# analog.net
KiCad netlist of a schematic drawn in EAGLE
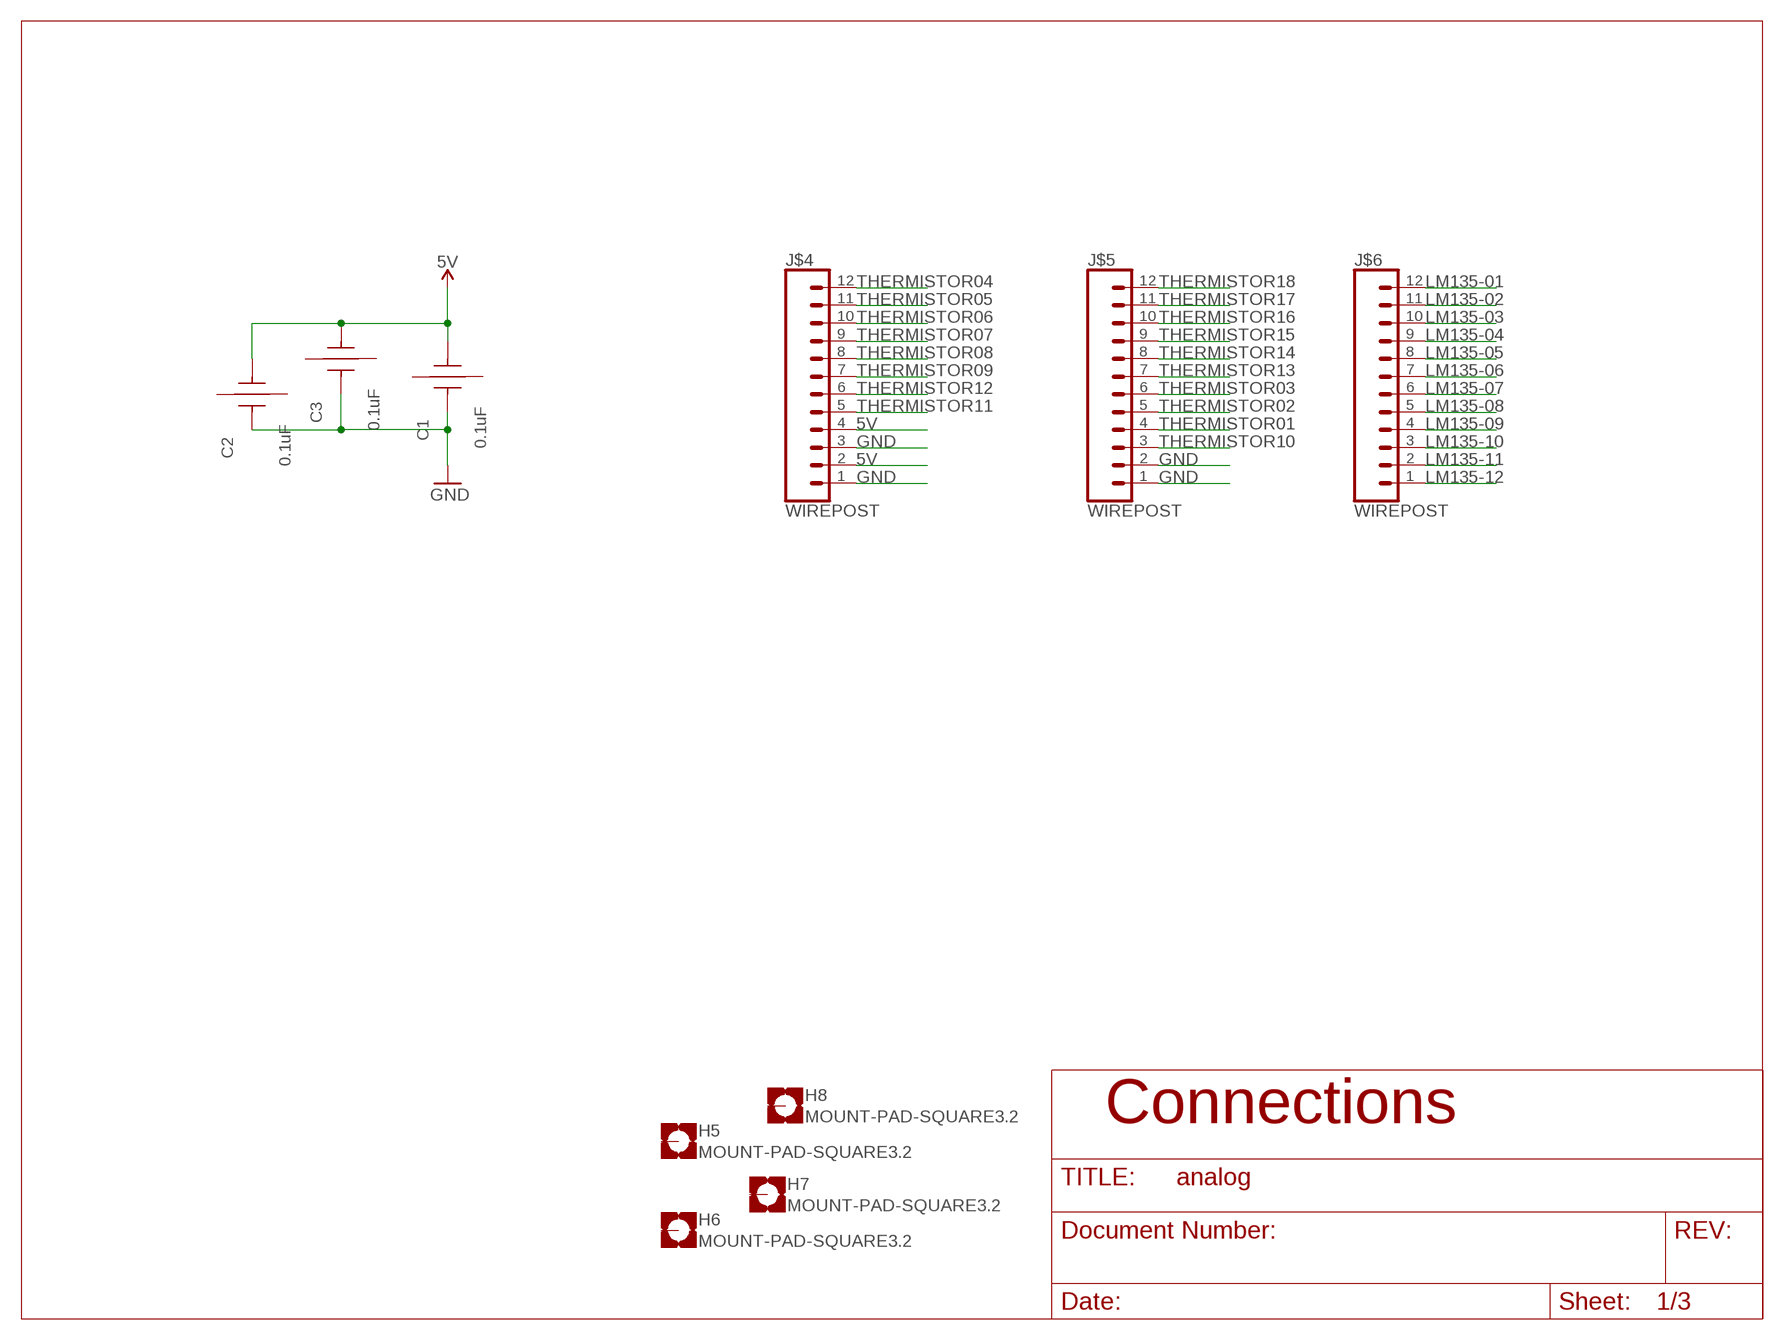
[diagram p0: schematic, sheet 1]
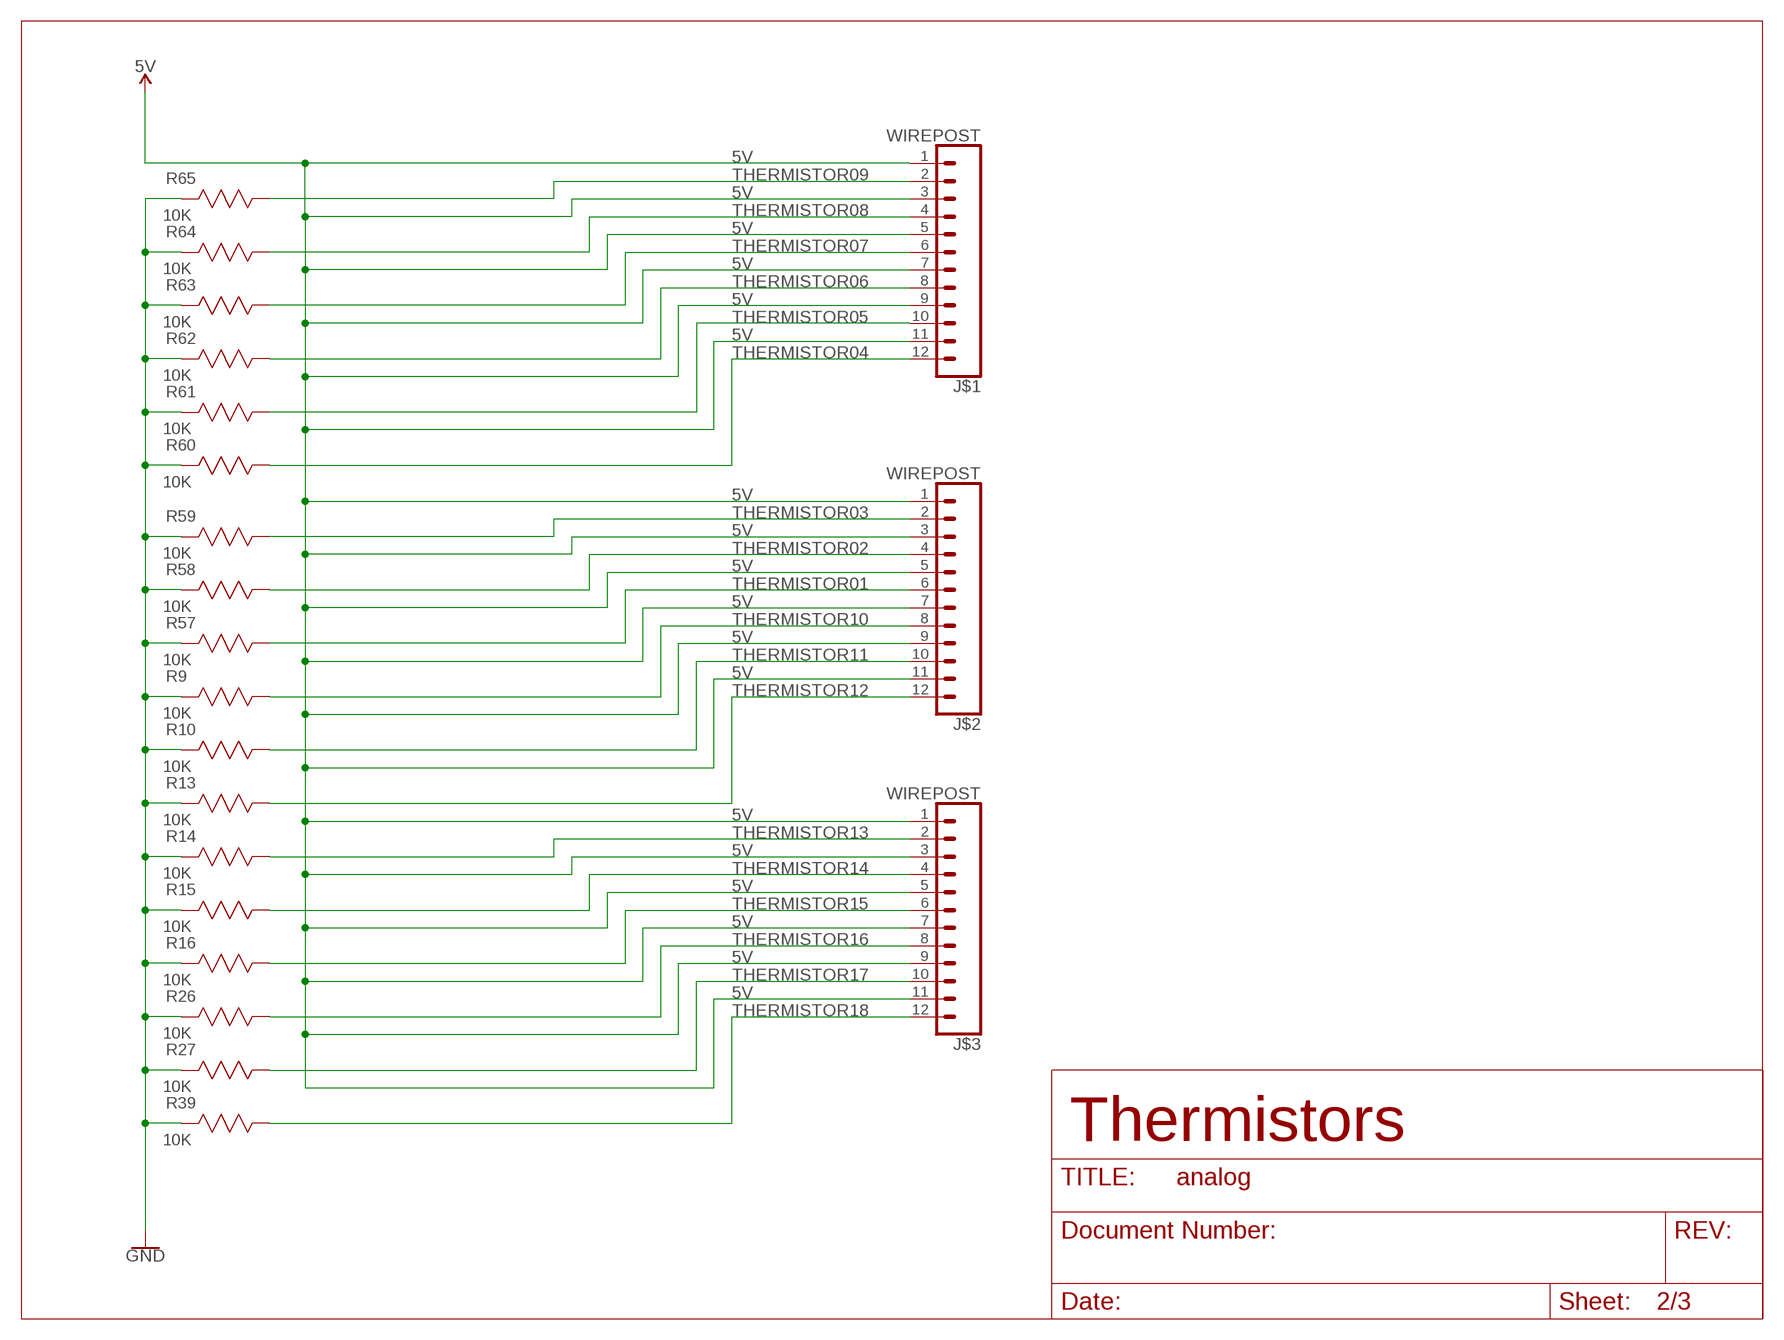
[diagram p1: schematic, sheet 2]
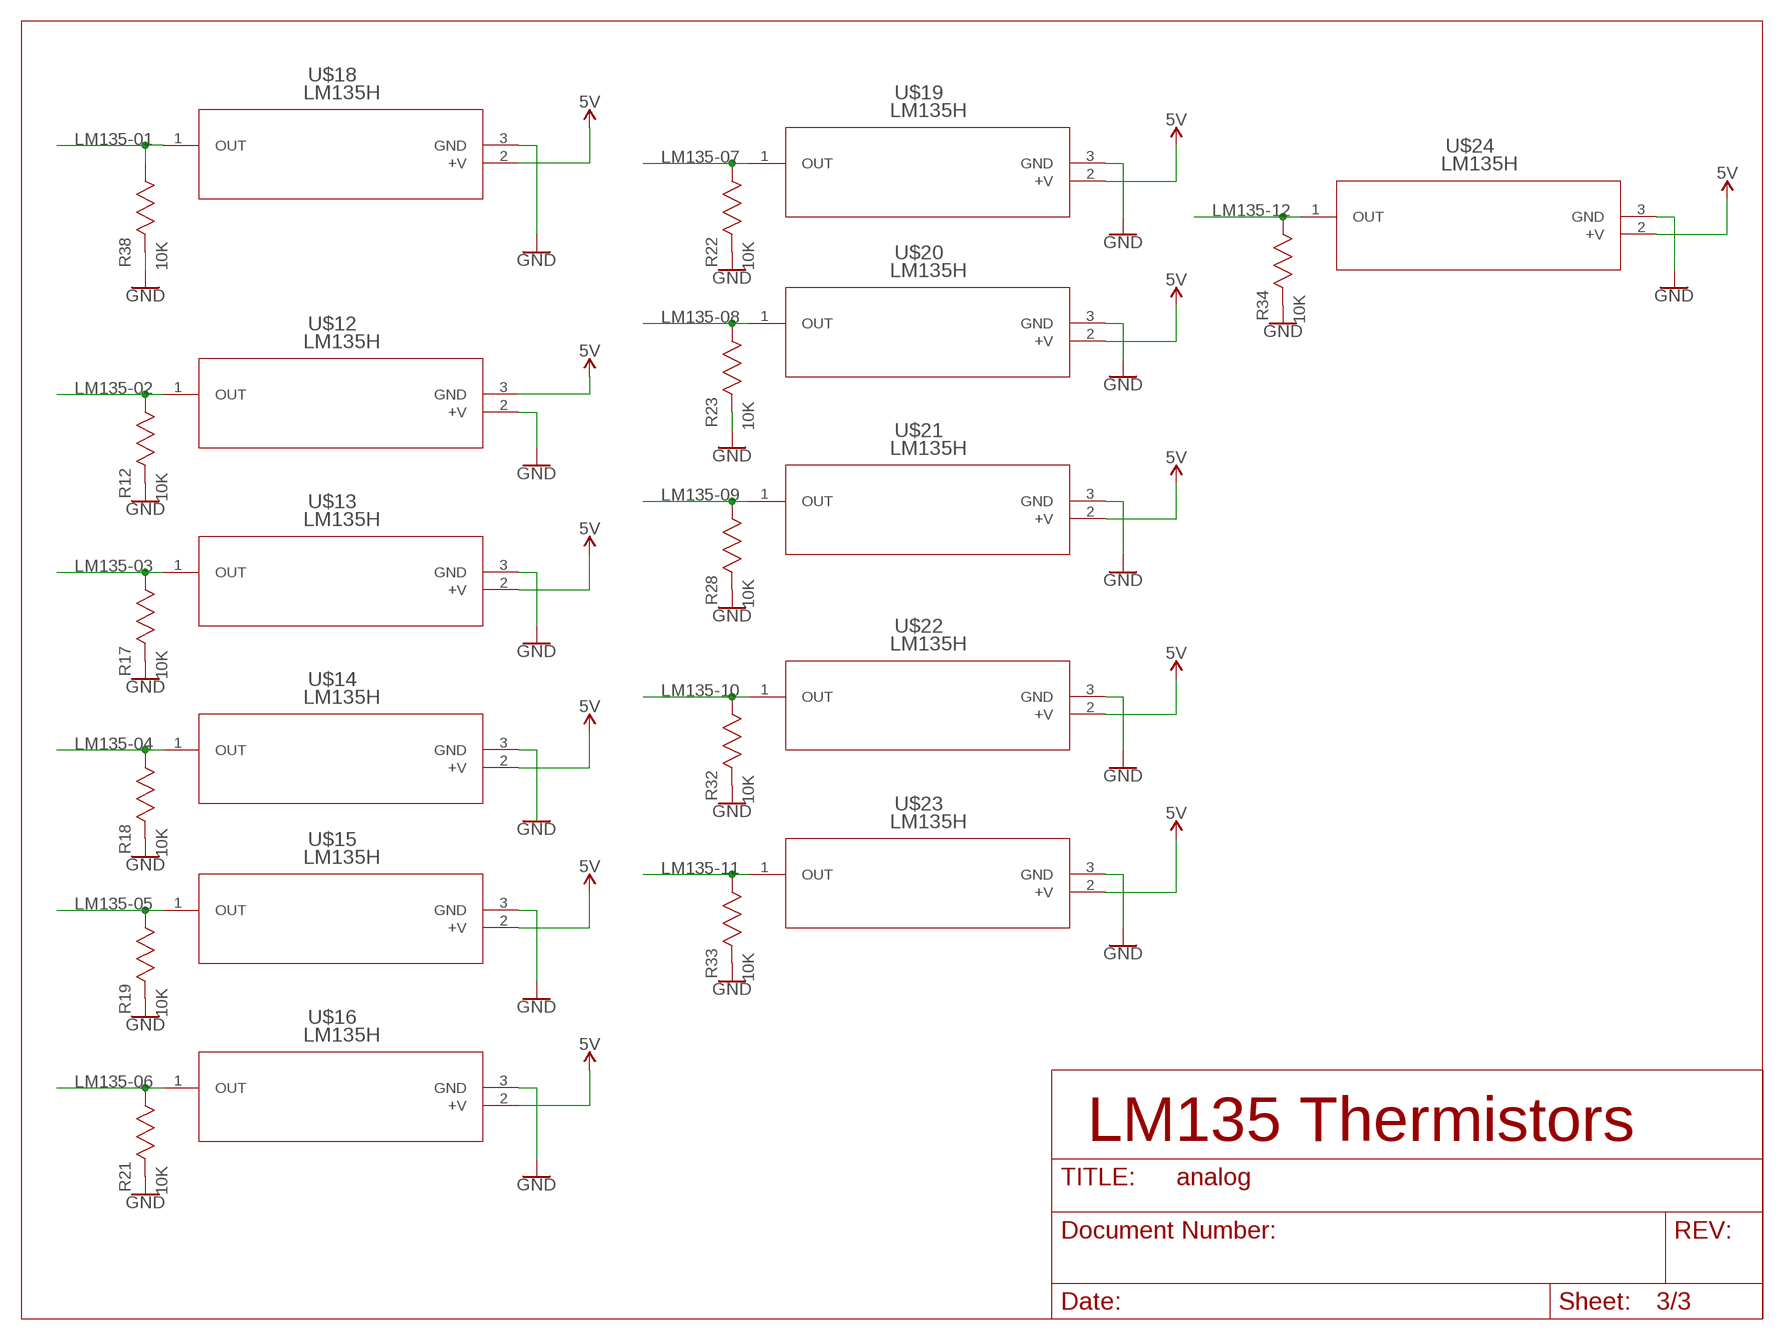
[diagram p2: schematic, sheet 3]

(export (version "E")
  (design (tool "Eeschema 10.0.6"))
  (components
    (comp (ref "J$1")
      (value "WIREPOST")
      (footprint "eagle-import:WIREWRAPPOST")
      (libsource (lib "eagle-import") (part "WIREPOST"))
    )
    (comp (ref "J$2")
      (value "WIREPOST")
      (footprint "eagle-import:WIREWRAPPOST")
      (libsource (lib "eagle-import") (part "WIREPOST"))
    )
    (comp (ref "J$3")
      (value "WIREPOST")
      (footprint "eagle-import:WIREWRAPPOST")
      (libsource (lib "eagle-import") (part "WIREPOST"))
    )
    (comp (ref "R9")
      (value "10K")
      (footprint "eagle-import:RC0603N")
      (fields (field (name "MANUFACTURER_PART_NUMBER") "RC0603JR0710KL"))
      (libsource (lib "eagle-import") (part "RC0603JR-0710KL"))
    )
    (comp (ref "R10")
      (value "10K")
      (footprint "eagle-import:RC0603N")
      (fields (field (name "MANUFACTURER_PART_NUMBER") "RC0603JR0710KL"))
      (libsource (lib "eagle-import") (part "RC0603JR-0710KL"))
    )
    (comp (ref "R13")
      (value "10K")
      (footprint "eagle-import:RC0603N")
      (fields (field (name "MANUFACTURER_PART_NUMBER") "RC0603JR0710KL"))
      (libsource (lib "eagle-import") (part "RC0603JR-0710KL"))
    )
    (comp (ref "R14")
      (value "10K")
      (footprint "eagle-import:RC0603N")
      (fields (field (name "MANUFACTURER_PART_NUMBER") "RC0603JR0710KL"))
      (libsource (lib "eagle-import") (part "RC0603JR-0710KL"))
    )
    (comp (ref "R15")
      (value "10K")
      (footprint "eagle-import:RC0603N")
      (fields (field (name "MANUFACTURER_PART_NUMBER") "RC0603JR0710KL"))
      (libsource (lib "eagle-import") (part "RC0603JR-0710KL"))
    )
    (comp (ref "R16")
      (value "10K")
      (footprint "eagle-import:RC0603N")
      (fields (field (name "MANUFACTURER_PART_NUMBER") "RC0603JR0710KL"))
      (libsource (lib "eagle-import") (part "RC0603JR-0710KL"))
    )
    (comp (ref "R26")
      (value "10K")
      (footprint "eagle-import:RC0603N")
      (fields (field (name "MANUFACTURER_PART_NUMBER") "RC0603JR0710KL"))
      (libsource (lib "eagle-import") (part "RC0603JR-0710KL"))
    )
    (comp (ref "R27")
      (value "10K")
      (footprint "eagle-import:RC0603N")
      (fields (field (name "MANUFACTURER_PART_NUMBER") "RC0603JR0710KL"))
      (libsource (lib "eagle-import") (part "RC0603JR-0710KL"))
    )
    (comp (ref "R39")
      (value "10K")
      (footprint "eagle-import:RC0603N")
      (fields (field (name "MANUFACTURER_PART_NUMBER") "RC0603JR0710KL"))
      (libsource (lib "eagle-import") (part "RC0603JR-0710KL"))
    )
    (comp (ref "R57")
      (value "10K")
      (footprint "eagle-import:RC0603N")
      (fields (field (name "MANUFACTURER_PART_NUMBER") "RC0603JR0710KL"))
      (libsource (lib "eagle-import") (part "RC0603JR-0710KL"))
    )
    (comp (ref "R58")
      (value "10K")
      (footprint "eagle-import:RC0603N")
      (fields (field (name "MANUFACTURER_PART_NUMBER") "RC0603JR0710KL"))
      (libsource (lib "eagle-import") (part "RC0603JR-0710KL"))
    )
    (comp (ref "R59")
      (value "10K")
      (footprint "eagle-import:RC0603N")
      (fields (field (name "MANUFACTURER_PART_NUMBER") "RC0603JR0710KL"))
      (libsource (lib "eagle-import") (part "RC0603JR-0710KL"))
    )
    (comp (ref "R60")
      (value "10K")
      (footprint "eagle-import:RC0603N")
      (fields (field (name "MANUFACTURER_PART_NUMBER") "RC0603JR0710KL"))
      (libsource (lib "eagle-import") (part "RC0603JR-0710KL"))
    )
    (comp (ref "R61")
      (value "10K")
      (footprint "eagle-import:RC0603N")
      (fields (field (name "MANUFACTURER_PART_NUMBER") "RC0603JR0710KL"))
      (libsource (lib "eagle-import") (part "RC0603JR-0710KL"))
    )
    (comp (ref "R62")
      (value "10K")
      (footprint "eagle-import:RC0603N")
      (fields (field (name "MANUFACTURER_PART_NUMBER") "RC0603JR0710KL"))
      (libsource (lib "eagle-import") (part "RC0603JR-0710KL"))
    )
    (comp (ref "R63")
      (value "10K")
      (footprint "eagle-import:RC0603N")
      (fields (field (name "MANUFACTURER_PART_NUMBER") "RC0603JR0710KL"))
      (libsource (lib "eagle-import") (part "RC0603JR-0710KL"))
    )
    (comp (ref "R64")
      (value "10K")
      (footprint "eagle-import:RC0603N")
      (fields (field (name "MANUFACTURER_PART_NUMBER") "RC0603JR0710KL"))
      (libsource (lib "eagle-import") (part "RC0603JR-0710KL"))
    )
    (comp (ref "R65")
      (value "10K")
      (footprint "eagle-import:RC0603N")
      (fields (field (name "MANUFACTURER_PART_NUMBER") "RC0603JR0710KL"))
      (libsource (lib "eagle-import") (part "RC0603JR-0710KL"))
    )
    (comp (ref "C1")
      (value "0.1uF")
      (footprint "eagle-import:X14")
      (fields (field (name "MANUFACTURER_PART_NUMBER") "100X14W104MV4T"))
      (libsource (lib "eagle-import") (part "100X14W104MV4T"))
    )
    (comp (ref "C2")
      (value "0.1uF")
      (footprint "eagle-import:X14")
      (fields (field (name "MANUFACTURER_PART_NUMBER") "100X14W104MV4T"))
      (libsource (lib "eagle-import") (part "100X14W104MV4T"))
    )
    (comp (ref "C3")
      (value "0.1uF")
      (footprint "eagle-import:X14")
      (fields (field (name "MANUFACTURER_PART_NUMBER") "100X14W104MV4T"))
      (libsource (lib "eagle-import") (part "100X14W104MV4T"))
    )
    (comp (ref "H5")
      (value "MOUNT-PAD-SQUARE3.2")
      (footprint "eagle-import:3,2-PAD-SQUARE")
      (libsource (lib "eagle-import") (part "MOUNT-PAD-SQUARE3.2"))
    )
    (comp (ref "H6")
      (value "MOUNT-PAD-SQUARE3.2")
      (footprint "eagle-import:3,2-PAD-SQUARE")
      (libsource (lib "eagle-import") (part "MOUNT-PAD-SQUARE3.2"))
    )
    (comp (ref "H7")
      (value "MOUNT-PAD-SQUARE3.2")
      (footprint "eagle-import:3,2-PAD-SQUARE")
      (libsource (lib "eagle-import") (part "MOUNT-PAD-SQUARE3.2"))
    )
    (comp (ref "H8")
      (value "MOUNT-PAD-SQUARE3.2")
      (footprint "eagle-import:3,2-PAD-SQUARE")
      (libsource (lib "eagle-import") (part "MOUNT-PAD-SQUARE3.2"))
    )
    (comp (ref "J$4")
      (value "WIREPOST")
      (footprint "eagle-import:WIREWRAPPOST")
      (libsource (lib "eagle-import") (part "WIREPOST"))
    )
    (comp (ref "J$5")
      (value "WIREPOST")
      (footprint "eagle-import:WIREWRAPPOST")
      (libsource (lib "eagle-import") (part "WIREPOST"))
    )
    (comp (ref "J$6")
      (value "WIREPOST")
      (footprint "eagle-import:WIREWRAPPOST")
      (libsource (lib "eagle-import") (part "WIREPOST"))
    )
    (comp (ref "R12")
      (value "10K")
      (footprint "eagle-import:RC0603N")
      (fields (field (name "MANUFACTURER_PART_NUMBER") "RC0603JR0710KL"))
      (libsource (lib "eagle-import") (part "RC0603JR-0710KL"))
    )
    (comp (ref "R17")
      (value "10K")
      (footprint "eagle-import:RC0603N")
      (fields (field (name "MANUFACTURER_PART_NUMBER") "RC0603JR0710KL"))
      (libsource (lib "eagle-import") (part "RC0603JR-0710KL"))
    )
    (comp (ref "R18")
      (value "10K")
      (footprint "eagle-import:RC0603N")
      (fields (field (name "MANUFACTURER_PART_NUMBER") "RC0603JR0710KL"))
      (libsource (lib "eagle-import") (part "RC0603JR-0710KL"))
    )
    (comp (ref "R19")
      (value "10K")
      (footprint "eagle-import:RC0603N")
      (fields (field (name "MANUFACTURER_PART_NUMBER") "RC0603JR0710KL"))
      (libsource (lib "eagle-import") (part "RC0603JR-0710KL"))
    )
    (comp (ref "R21")
      (value "10K")
      (footprint "eagle-import:RC0603N")
      (fields (field (name "MANUFACTURER_PART_NUMBER") "RC0603JR0710KL"))
      (libsource (lib "eagle-import") (part "RC0603JR-0710KL"))
    )
    (comp (ref "R22")
      (value "10K")
      (footprint "eagle-import:RC0603N")
      (fields (field (name "MANUFACTURER_PART_NUMBER") "RC0603JR0710KL"))
      (libsource (lib "eagle-import") (part "RC0603JR-0710KL"))
    )
    (comp (ref "R23")
      (value "10K")
      (footprint "eagle-import:RC0603N")
      (fields (field (name "MANUFACTURER_PART_NUMBER") "RC0603JR0710KL"))
      (libsource (lib "eagle-import") (part "RC0603JR-0710KL"))
    )
    (comp (ref "R28")
      (value "10K")
      (footprint "eagle-import:RC0603N")
      (fields (field (name "MANUFACTURER_PART_NUMBER") "RC0603JR0710KL"))
      (libsource (lib "eagle-import") (part "RC0603JR-0710KL"))
    )
    (comp (ref "R32")
      (value "10K")
      (footprint "eagle-import:RC0603N")
      (fields (field (name "MANUFACTURER_PART_NUMBER") "RC0603JR0710KL"))
      (libsource (lib "eagle-import") (part "RC0603JR-0710KL"))
    )
    (comp (ref "R33")
      (value "10K")
      (footprint "eagle-import:RC0603N")
      (fields (field (name "MANUFACTURER_PART_NUMBER") "RC0603JR0710KL"))
      (libsource (lib "eagle-import") (part "RC0603JR-0710KL"))
    )
    (comp (ref "R34")
      (value "10K")
      (footprint "eagle-import:RC0603N")
      (fields (field (name "MANUFACTURER_PART_NUMBER") "RC0603JR0710KL"))
      (libsource (lib "eagle-import") (part "RC0603JR-0710KL"))
    )
    (comp (ref "R38")
      (value "10K")
      (footprint "eagle-import:RC0603N")
      (fields (field (name "MANUFACTURER_PART_NUMBER") "RC0603JR0710KL"))
      (libsource (lib "eagle-import") (part "RC0603JR-0710KL"))
    )
    (comp (ref "U$12")
      (value "LM135H")
      (footprint "eagle-import:TO46")
      (libsource (lib "eagle-import") (part "LM135H"))
    )
    (comp (ref "U$13")
      (value "LM135H")
      (footprint "eagle-import:TO46")
      (libsource (lib "eagle-import") (part "LM135H"))
    )
    (comp (ref "U$14")
      (value "LM135H")
      (footprint "eagle-import:TO46")
      (libsource (lib "eagle-import") (part "LM135H"))
    )
    (comp (ref "U$15")
      (value "LM135H")
      (footprint "eagle-import:TO46")
      (libsource (lib "eagle-import") (part "LM135H"))
    )
    (comp (ref "U$16")
      (value "LM135H")
      (footprint "eagle-import:TO46")
      (libsource (lib "eagle-import") (part "LM135H"))
    )
    (comp (ref "U$18")
      (value "LM135H")
      (footprint "eagle-import:TO46")
      (libsource (lib "eagle-import") (part "LM135H"))
    )
    (comp (ref "U$19")
      (value "LM135H")
      (footprint "eagle-import:TO46")
      (libsource (lib "eagle-import") (part "LM135H"))
    )
    (comp (ref "U$20")
      (value "LM135H")
      (footprint "eagle-import:TO46")
      (libsource (lib "eagle-import") (part "LM135H"))
    )
    (comp (ref "U$21")
      (value "LM135H")
      (footprint "eagle-import:TO46")
      (libsource (lib "eagle-import") (part "LM135H"))
    )
    (comp (ref "U$22")
      (value "LM135H")
      (footprint "eagle-import:TO46")
      (libsource (lib "eagle-import") (part "LM135H"))
    )
    (comp (ref "U$23")
      (value "LM135H")
      (footprint "eagle-import:TO46")
      (libsource (lib "eagle-import") (part "LM135H"))
    )
    (comp (ref "U$24")
      (value "LM135H")
      (footprint "eagle-import:TO46")
      (libsource (lib "eagle-import") (part "LM135H"))
    )
  )
  (nets
    (net (code "1") (name "5V") (class "Default")
      (node (ref "C1") (pin "2") (pinfunction "22_2") (pintype "passive"))
      (node (ref "C2") (pin "2") (pinfunction "22_2") (pintype "passive"))
      (node (ref "C3") (pin "2") (pinfunction "22_2") (pintype "passive"))
      (node (ref "J$1") (pin "1") (pinfunction "1_1") (pintype "passive"))
      (node (ref "J$1") (pin "11") (pinfunction "11_11") (pintype "passive"))
      (node (ref "J$1") (pin "3") (pinfunction "3_3") (pintype "passive"))
      (node (ref "J$1") (pin "5") (pinfunction "5_5") (pintype "passive"))
      (node (ref "J$1") (pin "7") (pinfunction "7_7") (pintype "passive"))
      (node (ref "J$1") (pin "9") (pinfunction "9_9") (pintype "passive"))
      (node (ref "J$2") (pin "1") (pinfunction "1_1") (pintype "passive"))
      (node (ref "J$2") (pin "11") (pinfunction "11_11") (pintype "passive"))
      (node (ref "J$2") (pin "3") (pinfunction "3_3") (pintype "passive"))
      (node (ref "J$2") (pin "5") (pinfunction "5_5") (pintype "passive"))
      (node (ref "J$2") (pin "7") (pinfunction "7_7") (pintype "passive"))
      (node (ref "J$2") (pin "9") (pinfunction "9_9") (pintype "passive"))
      (node (ref "J$3") (pin "1") (pinfunction "1_1") (pintype "passive"))
      (node (ref "J$3") (pin "11") (pinfunction "11_11") (pintype "passive"))
      (node (ref "J$3") (pin "3") (pinfunction "3_3") (pintype "passive"))
      (node (ref "J$3") (pin "5") (pinfunction "5_5") (pintype "passive"))
      (node (ref "J$3") (pin "7") (pinfunction "7_7") (pintype "passive"))
      (node (ref "J$3") (pin "9") (pinfunction "9_9") (pintype "passive"))
      (node (ref "J$4") (pin "2") (pinfunction "2_2") (pintype "passive"))
      (node (ref "J$4") (pin "4") (pinfunction "4_4") (pintype "passive"))
      (node (ref "U$12") (pin "3") (pinfunction "GND_3") (pintype "passive"))
      (node (ref "U$13") (pin "2") (pinfunction "+V_2") (pintype "passive"))
      (node (ref "U$14") (pin "2") (pinfunction "+V_2") (pintype "passive"))
      (node (ref "U$15") (pin "2") (pinfunction "+V_2") (pintype "passive"))
      (node (ref "U$16") (pin "2") (pinfunction "+V_2") (pintype "passive"))
      (node (ref "U$18") (pin "2") (pinfunction "+V_2") (pintype "passive"))
      (node (ref "U$19") (pin "2") (pinfunction "+V_2") (pintype "passive"))
      (node (ref "U$20") (pin "2") (pinfunction "+V_2") (pintype "passive"))
      (node (ref "U$21") (pin "2") (pinfunction "+V_2") (pintype "passive"))
      (node (ref "U$22") (pin "2") (pinfunction "+V_2") (pintype "passive"))
      (node (ref "U$23") (pin "2") (pinfunction "+V_2") (pintype "passive"))
      (node (ref "U$24") (pin "2") (pinfunction "+V_2") (pintype "passive"))
    )
    (net (code "2") (name "GND") (class "Default")
      (node (ref "C1") (pin "1") (pinfunction "11_1") (pintype "passive"))
      (node (ref "C2") (pin "1") (pinfunction "11_1") (pintype "passive"))
      (node (ref "C3") (pin "1") (pinfunction "11_1") (pintype "passive"))
      (node (ref "J$4") (pin "1") (pinfunction "1_1") (pintype "passive"))
      (node (ref "J$4") (pin "3") (pinfunction "3_3") (pintype "passive"))
      (node (ref "J$5") (pin "1") (pinfunction "1_1") (pintype "passive"))
      (node (ref "J$5") (pin "2") (pinfunction "2_2") (pintype "passive"))
      (node (ref "R10") (pin "2") (pinfunction "22_2") (pintype "passive"))
      (node (ref "R12") (pin "2") (pinfunction "22_2") (pintype "passive"))
      (node (ref "R13") (pin "2") (pinfunction "22_2") (pintype "passive"))
      (node (ref "R14") (pin "2") (pinfunction "22_2") (pintype "passive"))
      (node (ref "R15") (pin "2") (pinfunction "22_2") (pintype "passive"))
      (node (ref "R16") (pin "2") (pinfunction "22_2") (pintype "passive"))
      (node (ref "R17") (pin "2") (pinfunction "22_2") (pintype "passive"))
      (node (ref "R18") (pin "2") (pinfunction "22_2") (pintype "passive"))
      (node (ref "R19") (pin "2") (pinfunction "22_2") (pintype "passive"))
      (node (ref "R21") (pin "2") (pinfunction "22_2") (pintype "passive"))
      (node (ref "R22") (pin "2") (pinfunction "22_2") (pintype "passive"))
      (node (ref "R23") (pin "2") (pinfunction "22_2") (pintype "passive"))
      (node (ref "R26") (pin "2") (pinfunction "22_2") (pintype "passive"))
      (node (ref "R27") (pin "2") (pinfunction "22_2") (pintype "passive"))
      (node (ref "R28") (pin "2") (pinfunction "22_2") (pintype "passive"))
      (node (ref "R32") (pin "2") (pinfunction "22_2") (pintype "passive"))
      (node (ref "R33") (pin "2") (pinfunction "22_2") (pintype "passive"))
      (node (ref "R34") (pin "2") (pinfunction "22_2") (pintype "passive"))
      (node (ref "R38") (pin "2") (pinfunction "22_2") (pintype "passive"))
      (node (ref "R39") (pin "2") (pinfunction "22_2") (pintype "passive"))
      (node (ref "R57") (pin "2") (pinfunction "22_2") (pintype "passive"))
      (node (ref "R58") (pin "2") (pinfunction "22_2") (pintype "passive"))
      (node (ref "R59") (pin "2") (pinfunction "22_2") (pintype "passive"))
      (node (ref "R60") (pin "2") (pinfunction "22_2") (pintype "passive"))
      (node (ref "R61") (pin "2") (pinfunction "22_2") (pintype "passive"))
      (node (ref "R62") (pin "2") (pinfunction "22_2") (pintype "passive"))
      (node (ref "R63") (pin "2") (pinfunction "22_2") (pintype "passive"))
      (node (ref "R64") (pin "2") (pinfunction "22_2") (pintype "passive"))
      (node (ref "R65") (pin "2") (pinfunction "22_2") (pintype "passive"))
      (node (ref "R9") (pin "2") (pinfunction "22_2") (pintype "passive"))
      (node (ref "U$12") (pin "2") (pinfunction "+V_2") (pintype "passive"))
      (node (ref "U$13") (pin "3") (pinfunction "GND_3") (pintype "passive"))
      (node (ref "U$14") (pin "3") (pinfunction "GND_3") (pintype "passive"))
      (node (ref "U$15") (pin "3") (pinfunction "GND_3") (pintype "passive"))
      (node (ref "U$16") (pin "3") (pinfunction "GND_3") (pintype "passive"))
      (node (ref "U$18") (pin "3") (pinfunction "GND_3") (pintype "passive"))
      (node (ref "U$19") (pin "3") (pinfunction "GND_3") (pintype "passive"))
      (node (ref "U$20") (pin "3") (pinfunction "GND_3") (pintype "passive"))
      (node (ref "U$21") (pin "3") (pinfunction "GND_3") (pintype "passive"))
      (node (ref "U$22") (pin "3") (pinfunction "GND_3") (pintype "passive"))
      (node (ref "U$23") (pin "3") (pinfunction "GND_3") (pintype "passive"))
      (node (ref "U$24") (pin "3") (pinfunction "GND_3") (pintype "passive"))
    )
    (net (code "3") (name "LM135-01") (class "Default")
      (node (ref "J$6") (pin "12") (pinfunction "12_12") (pintype "passive"))
      (node (ref "R38") (pin "1") (pinfunction "11_1") (pintype "passive"))
      (node (ref "U$18") (pin "1") (pinfunction "OUT_1") (pintype "passive"))
    )
    (net (code "4") (name "LM135-02") (class "Default")
      (node (ref "J$6") (pin "11") (pinfunction "11_11") (pintype "passive"))
      (node (ref "R12") (pin "1") (pinfunction "11_1") (pintype "passive"))
      (node (ref "U$12") (pin "1") (pinfunction "OUT_1") (pintype "passive"))
    )
    (net (code "5") (name "LM135-03") (class "Default")
      (node (ref "J$6") (pin "10") (pinfunction "10_10") (pintype "passive"))
      (node (ref "R17") (pin "1") (pinfunction "11_1") (pintype "passive"))
      (node (ref "U$13") (pin "1") (pinfunction "OUT_1") (pintype "passive"))
    )
    (net (code "6") (name "LM135-04") (class "Default")
      (node (ref "J$6") (pin "9") (pinfunction "9_9") (pintype "passive"))
      (node (ref "R18") (pin "1") (pinfunction "11_1") (pintype "passive"))
      (node (ref "U$14") (pin "1") (pinfunction "OUT_1") (pintype "passive"))
    )
    (net (code "7") (name "LM135-05") (class "Default")
      (node (ref "J$6") (pin "8") (pinfunction "8_8") (pintype "passive"))
      (node (ref "R19") (pin "1") (pinfunction "11_1") (pintype "passive"))
      (node (ref "U$15") (pin "1") (pinfunction "OUT_1") (pintype "passive"))
    )
    (net (code "8") (name "LM135-06") (class "Default")
      (node (ref "J$6") (pin "7") (pinfunction "7_7") (pintype "passive"))
      (node (ref "R21") (pin "1") (pinfunction "11_1") (pintype "passive"))
      (node (ref "U$16") (pin "1") (pinfunction "OUT_1") (pintype "passive"))
    )
    (net (code "9") (name "LM135-07") (class "Default")
      (node (ref "J$6") (pin "6") (pinfunction "6_6") (pintype "passive"))
      (node (ref "R22") (pin "1") (pinfunction "11_1") (pintype "passive"))
      (node (ref "U$19") (pin "1") (pinfunction "OUT_1") (pintype "passive"))
    )
    (net (code "10") (name "LM135-08") (class "Default")
      (node (ref "J$6") (pin "5") (pinfunction "5_5") (pintype "passive"))
      (node (ref "R23") (pin "1") (pinfunction "11_1") (pintype "passive"))
      (node (ref "U$20") (pin "1") (pinfunction "OUT_1") (pintype "passive"))
    )
    (net (code "11") (name "LM135-09") (class "Default")
      (node (ref "J$6") (pin "4") (pinfunction "4_4") (pintype "passive"))
      (node (ref "R28") (pin "1") (pinfunction "11_1") (pintype "passive"))
      (node (ref "U$21") (pin "1") (pinfunction "OUT_1") (pintype "passive"))
    )
    (net (code "12") (name "LM135-10") (class "Default")
      (node (ref "J$6") (pin "3") (pinfunction "3_3") (pintype "passive"))
      (node (ref "R32") (pin "1") (pinfunction "11_1") (pintype "passive"))
      (node (ref "U$22") (pin "1") (pinfunction "OUT_1") (pintype "passive"))
    )
    (net (code "13") (name "LM135-11") (class "Default")
      (node (ref "J$6") (pin "2") (pinfunction "2_2") (pintype "passive"))
      (node (ref "R33") (pin "1") (pinfunction "11_1") (pintype "passive"))
      (node (ref "U$23") (pin "1") (pinfunction "OUT_1") (pintype "passive"))
    )
    (net (code "14") (name "LM135-12") (class "Default")
      (node (ref "J$6") (pin "1") (pinfunction "1_1") (pintype "passive"))
      (node (ref "R34") (pin "1") (pinfunction "11_1") (pintype "passive"))
      (node (ref "U$24") (pin "1") (pinfunction "OUT_1") (pintype "passive"))
    )
    (net (code "15") (name "THERMISTOR01") (class "Default")
      (node (ref "J$2") (pin "6") (pinfunction "6_6") (pintype "passive"))
      (node (ref "J$5") (pin "4") (pinfunction "4_4") (pintype "passive"))
      (node (ref "R57") (pin "1") (pinfunction "11_1") (pintype "passive"))
    )
    (net (code "16") (name "THERMISTOR02") (class "Default")
      (node (ref "J$2") (pin "4") (pinfunction "4_4") (pintype "passive"))
      (node (ref "J$5") (pin "5") (pinfunction "5_5") (pintype "passive"))
      (node (ref "R58") (pin "1") (pinfunction "11_1") (pintype "passive"))
    )
    (net (code "17") (name "THERMISTOR03") (class "Default")
      (node (ref "J$2") (pin "2") (pinfunction "2_2") (pintype "passive"))
      (node (ref "J$5") (pin "6") (pinfunction "6_6") (pintype "passive"))
      (node (ref "R59") (pin "1") (pinfunction "11_1") (pintype "passive"))
    )
    (net (code "18") (name "THERMISTOR04") (class "Default")
      (node (ref "J$1") (pin "12") (pinfunction "12_12") (pintype "passive"))
      (node (ref "J$4") (pin "12") (pinfunction "12_12") (pintype "passive"))
      (node (ref "R60") (pin "1") (pinfunction "11_1") (pintype "passive"))
    )
    (net (code "19") (name "THERMISTOR05") (class "Default")
      (node (ref "J$1") (pin "10") (pinfunction "10_10") (pintype "passive"))
      (node (ref "J$4") (pin "11") (pinfunction "11_11") (pintype "passive"))
      (node (ref "R61") (pin "1") (pinfunction "11_1") (pintype "passive"))
    )
    (net (code "20") (name "THERMISTOR06") (class "Default")
      (node (ref "J$1") (pin "8") (pinfunction "8_8") (pintype "passive"))
      (node (ref "J$4") (pin "10") (pinfunction "10_10") (pintype "passive"))
      (node (ref "R62") (pin "1") (pinfunction "11_1") (pintype "passive"))
    )
    (net (code "21") (name "THERMISTOR07") (class "Default")
      (node (ref "J$1") (pin "6") (pinfunction "6_6") (pintype "passive"))
      (node (ref "J$4") (pin "9") (pinfunction "9_9") (pintype "passive"))
      (node (ref "R63") (pin "1") (pinfunction "11_1") (pintype "passive"))
    )
    (net (code "22") (name "THERMISTOR08") (class "Default")
      (node (ref "J$1") (pin "4") (pinfunction "4_4") (pintype "passive"))
      (node (ref "J$4") (pin "8") (pinfunction "8_8") (pintype "passive"))
      (node (ref "R64") (pin "1") (pinfunction "11_1") (pintype "passive"))
    )
    (net (code "23") (name "THERMISTOR09") (class "Default")
      (node (ref "J$1") (pin "2") (pinfunction "2_2") (pintype "passive"))
      (node (ref "J$4") (pin "7") (pinfunction "7_7") (pintype "passive"))
      (node (ref "R65") (pin "1") (pinfunction "11_1") (pintype "passive"))
    )
    (net (code "24") (name "THERMISTOR10") (class "Default")
      (node (ref "J$2") (pin "8") (pinfunction "8_8") (pintype "passive"))
      (node (ref "J$5") (pin "3") (pinfunction "3_3") (pintype "passive"))
      (node (ref "R9") (pin "1") (pinfunction "11_1") (pintype "passive"))
    )
    (net (code "25") (name "THERMISTOR11") (class "Default")
      (node (ref "J$2") (pin "10") (pinfunction "10_10") (pintype "passive"))
      (node (ref "J$4") (pin "5") (pinfunction "5_5") (pintype "passive"))
      (node (ref "R10") (pin "1") (pinfunction "11_1") (pintype "passive"))
    )
    (net (code "26") (name "THERMISTOR12") (class "Default")
      (node (ref "J$2") (pin "12") (pinfunction "12_12") (pintype "passive"))
      (node (ref "J$4") (pin "6") (pinfunction "6_6") (pintype "passive"))
      (node (ref "R13") (pin "1") (pinfunction "11_1") (pintype "passive"))
    )
    (net (code "27") (name "THERMISTOR13") (class "Default")
      (node (ref "J$3") (pin "2") (pinfunction "2_2") (pintype "passive"))
      (node (ref "J$5") (pin "7") (pinfunction "7_7") (pintype "passive"))
      (node (ref "R14") (pin "1") (pinfunction "11_1") (pintype "passive"))
    )
    (net (code "28") (name "THERMISTOR14") (class "Default")
      (node (ref "J$3") (pin "4") (pinfunction "4_4") (pintype "passive"))
      (node (ref "J$5") (pin "8") (pinfunction "8_8") (pintype "passive"))
      (node (ref "R15") (pin "1") (pinfunction "11_1") (pintype "passive"))
    )
    (net (code "29") (name "THERMISTOR15") (class "Default")
      (node (ref "J$3") (pin "6") (pinfunction "6_6") (pintype "passive"))
      (node (ref "J$5") (pin "9") (pinfunction "9_9") (pintype "passive"))
      (node (ref "R16") (pin "1") (pinfunction "11_1") (pintype "passive"))
    )
    (net (code "30") (name "THERMISTOR16") (class "Default")
      (node (ref "J$3") (pin "8") (pinfunction "8_8") (pintype "passive"))
      (node (ref "J$5") (pin "10") (pinfunction "10_10") (pintype "passive"))
      (node (ref "R26") (pin "1") (pinfunction "11_1") (pintype "passive"))
    )
    (net (code "31") (name "THERMISTOR17") (class "Default")
      (node (ref "J$3") (pin "10") (pinfunction "10_10") (pintype "passive"))
      (node (ref "J$5") (pin "11") (pinfunction "11_11") (pintype "passive"))
      (node (ref "R27") (pin "1") (pinfunction "11_1") (pintype "passive"))
    )
    (net (code "32") (name "THERMISTOR18") (class "Default")
      (node (ref "J$3") (pin "12") (pinfunction "12_12") (pintype "passive"))
      (node (ref "J$5") (pin "12") (pinfunction "12_12") (pintype "passive"))
      (node (ref "R39") (pin "1") (pinfunction "11_1") (pintype "passive"))
    )
    (net (code "33") (name "unconnected-(C1-33-Pad3)") (class "Default")
      (node (ref "C1") (pin "3") (pinfunction "33_3") (pintype "passive"))
    )
    (net (code "34") (name "unconnected-(C1-44-Pad4)") (class "Default")
      (node (ref "C1") (pin "4") (pinfunction "44_4") (pintype "passive"))
    )
    (net (code "35") (name "unconnected-(C2-33-Pad3)") (class "Default")
      (node (ref "C2") (pin "3") (pinfunction "33_3") (pintype "passive"))
    )
    (net (code "36") (name "unconnected-(C2-44-Pad4)") (class "Default")
      (node (ref "C2") (pin "4") (pinfunction "44_4") (pintype "passive"))
    )
    (net (code "37") (name "unconnected-(C3-33-Pad3)") (class "Default")
      (node (ref "C3") (pin "3") (pinfunction "33_3") (pintype "passive"))
    )
    (net (code "38") (name "unconnected-(C3-44-Pad4)") (class "Default")
      (node (ref "C3") (pin "4") (pinfunction "44_4") (pintype "passive"))
    )
    (net (code "39") (name "unconnected-(H5-MOUNT-PadB3,2)") (class "Default")
      (node (ref "H5") (pin "B3,2") (pinfunction "MOUNT_B3,2") (pintype "passive"))
    )
    (net (code "40") (name "unconnected-(H6-MOUNT-PadB3,2)") (class "Default")
      (node (ref "H6") (pin "B3,2") (pinfunction "MOUNT_B3,2") (pintype "passive"))
    )
    (net (code "41") (name "unconnected-(H7-MOUNT-PadB3,2)") (class "Default")
      (node (ref "H7") (pin "B3,2") (pinfunction "MOUNT_B3,2") (pintype "passive"))
    )
    (net (code "42") (name "unconnected-(H8-MOUNT-PadB3,2)") (class "Default")
      (node (ref "H8") (pin "B3,2") (pinfunction "MOUNT_B3,2") (pintype "passive"))
    )
  )
)
